# ProPrj_RetroGame_2024-09-02_00-02-09_202.net
KiCad netlist of a schematic drawn in EasyEDA Pro
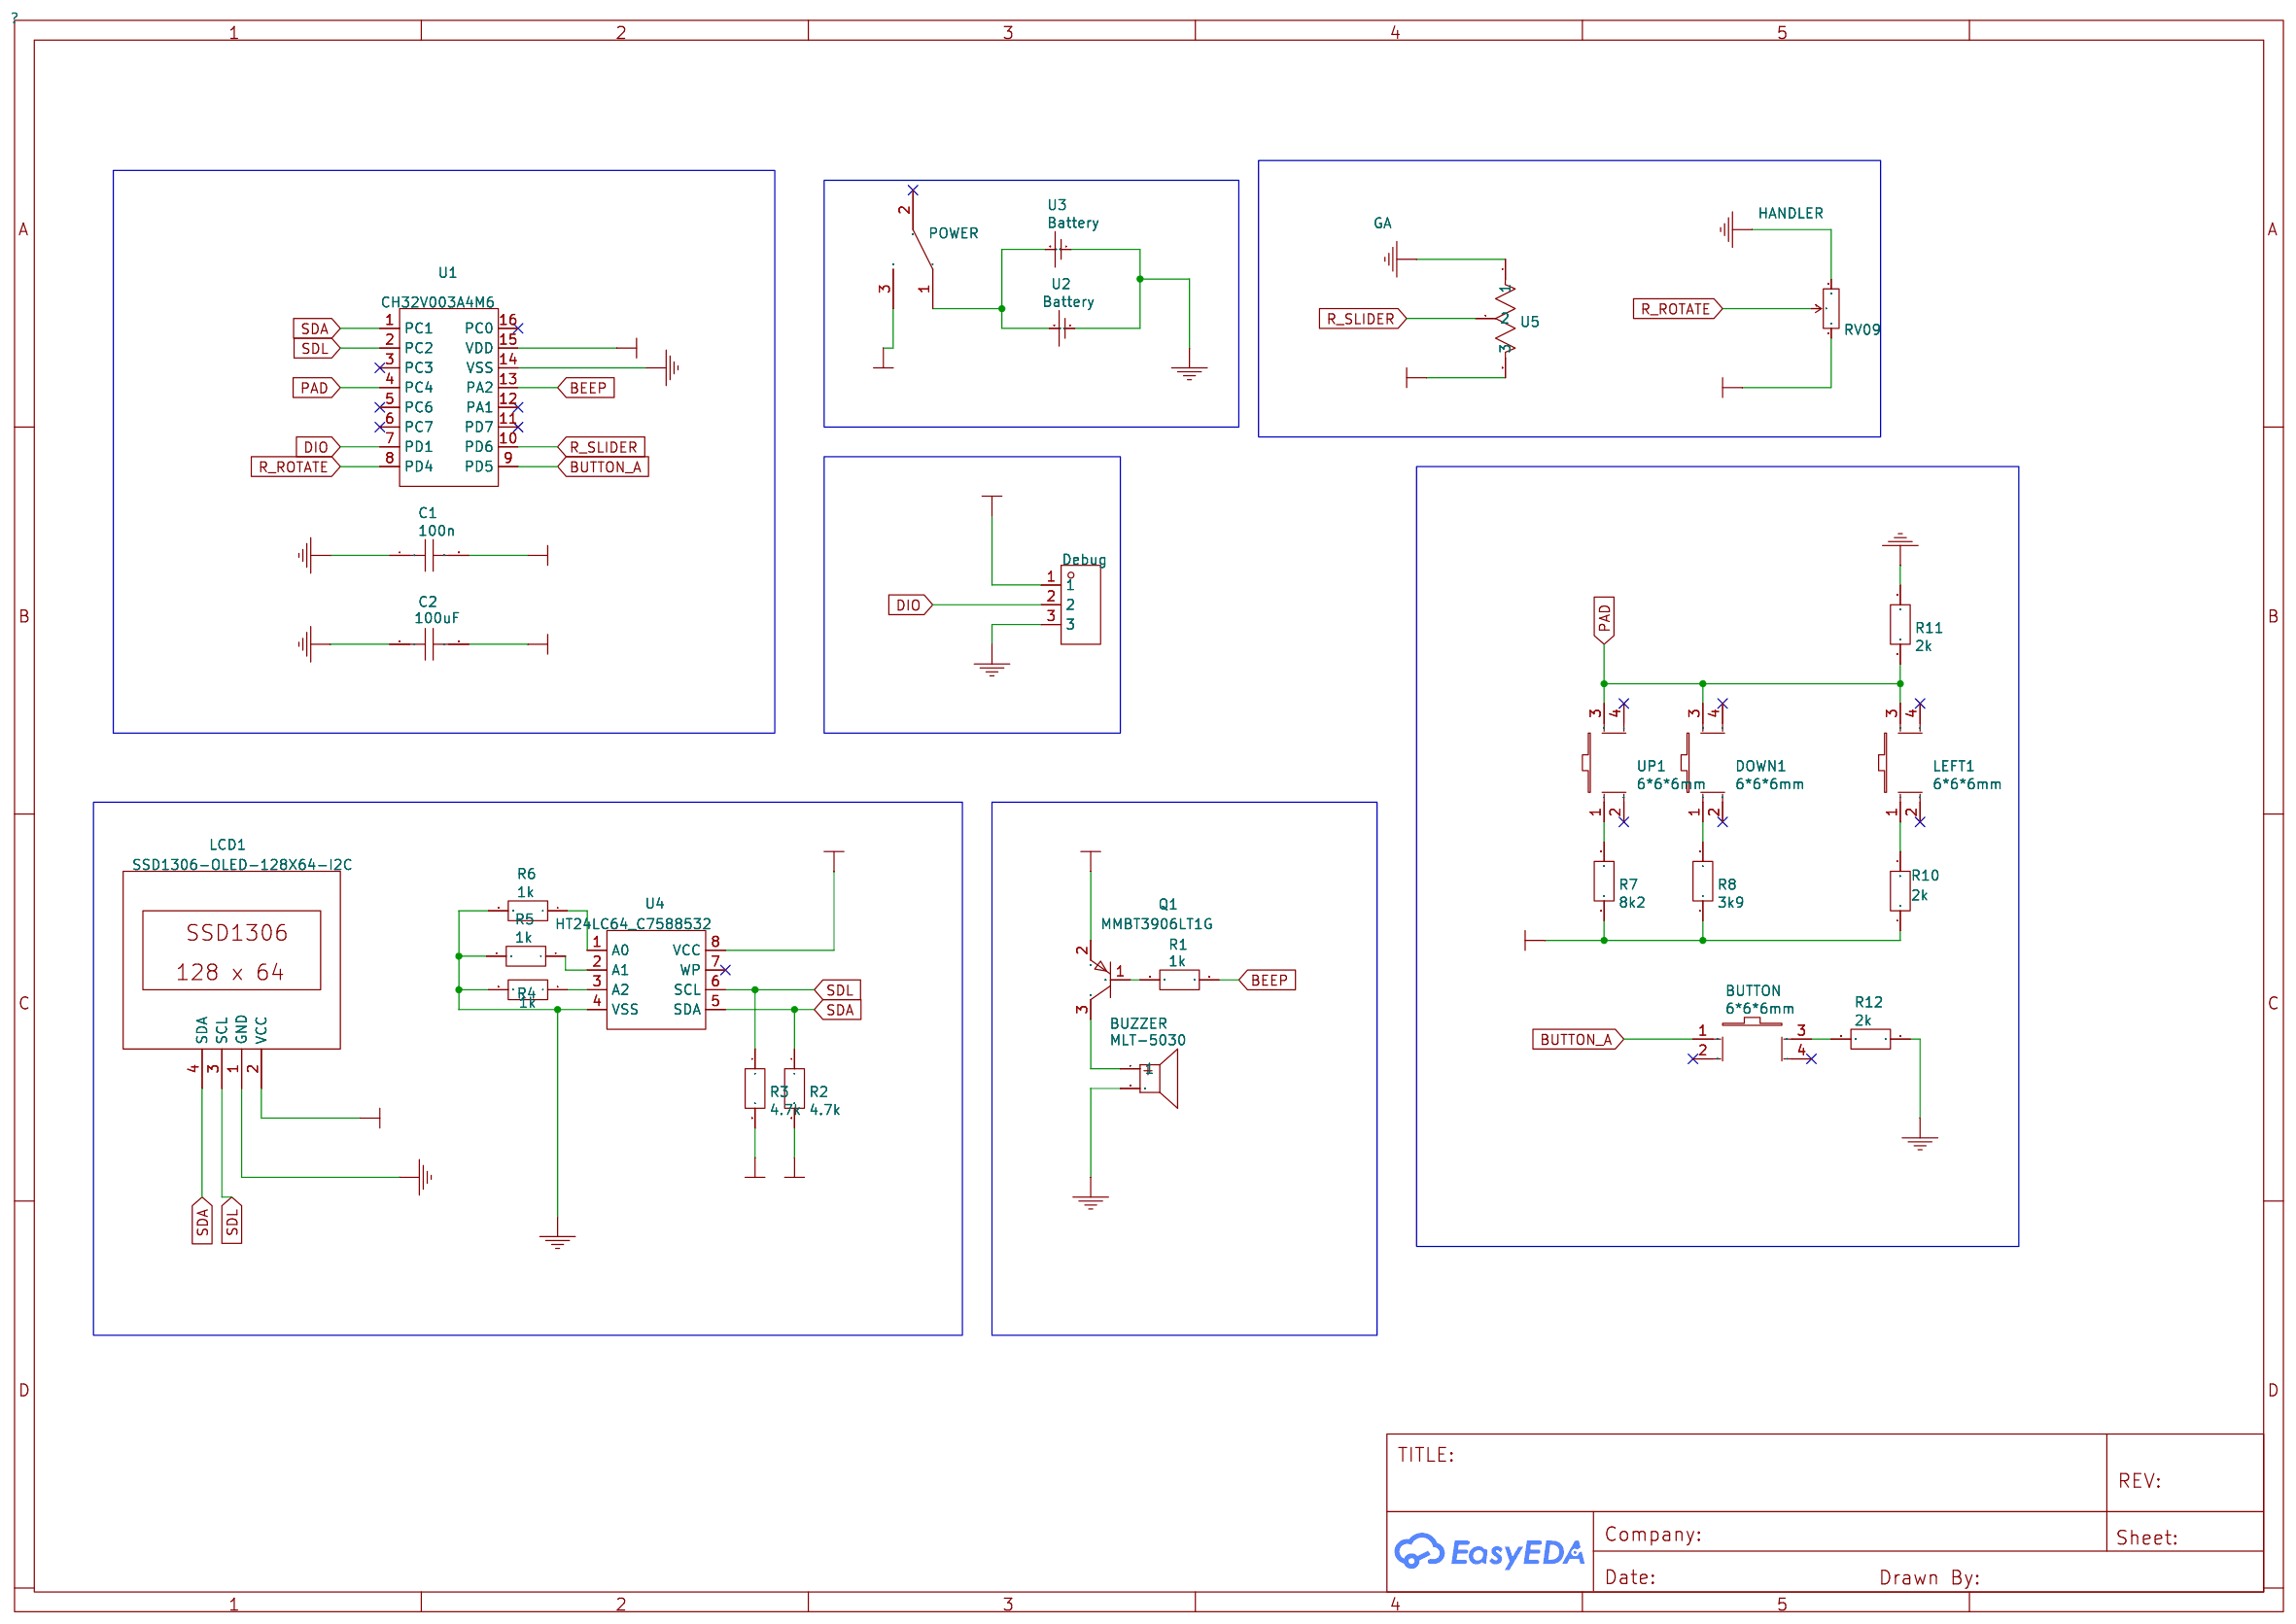
[diagram p0: schematic sheet]

(export (version "E")
  (design (tool "Eeschema 10.0.6"))
  (components
    (comp (ref "BUTTON")
      (value "6*6*6mm")
      (footprint "easyedapro:KEY-6.0*6.0")
      (fields
        (field (name "Manufacturer Part") "SMD Tactile Switch6*6*6mm")
        (field (name "Manufacturer") "ReliaPro")
      )
      (libsource (lib "easyedapro") (part "6*6*6mm"))
    )
    (comp (ref "BUZZER")
      (value "MLT-5030")
      (footprint "easyedapro:B-5.2*5.2")
      (fields (field (name "Manufacturer") "HNDZ"))
      (libsource (lib "easyedapro") (part "MLT-5030"))
    )
    (comp (ref "C1")
      (value "100n")
      (footprint "easyedapro:C0603")
      (libsource (lib "easyedapro") (part "100n"))
    )
    (comp (ref "C2")
      (value "100uF")
      (footprint "easyedapro:C0603")
      (libsource (lib "easyedapro") (part "100uF"))
    )
    (comp (ref "Debug")
      (value "~")
      (footprint "easyedapro:HDR-TH_3P-P2.54-V-F")
      (libsource (lib "easyedapro") (part "PM254V-11-03-H85"))
    )
    (comp (ref "DOWN1")
      (value "6*6*6mm")
      (footprint "easyedapro:KEY-6.0*6.0")
      (fields
        (field (name "Manufacturer Part") "SMD Tactile Switch6*6*6mm")
        (field (name "Manufacturer") "ReliaPro")
      )
      (libsource (lib "easyedapro") (part "6*6*6mm"))
    )
    (comp (ref "HANDLER")
      (value "RV09")
      (footprint "easyedapro:RV09")
      (libsource (lib "easyedapro") (part "RV09"))
    )
    (comp (ref "LCD1")
      (value "SSD1306-OLED-128X64-I2C")
      (footprint "easyedapro:SSD1306-OLED-128X64-I2C")
      (libsource (lib "easyedapro") (part "SSD1306-OLED-128X64-I2C"))
    )
    (comp (ref "LEFT1")
      (value "6*6*6mm")
      (footprint "easyedapro:KEY-6.0*6.0")
      (fields
        (field (name "Manufacturer Part") "SMD Tactile Switch6*6*6mm")
        (field (name "Manufacturer") "ReliaPro")
      )
      (libsource (lib "easyedapro") (part "6*6*6mm"))
    )
    (comp (ref "POWER")
      (value "MINI SLIDE SWITCH")
      (footprint "easyedapro:MINI SLIDE SWITCH SPDT - 3PİN - 2.54MM - 11X5.5MM - SS12D00G3-FP")
      (fields
        (field (name "Manufacturer Part") "COM-00102")
        (field (name "Manufacturer") "SparkFun Electronics")
      )
      (libsource (lib "easyedapro") (part "MINI SLIDE SWITCH"))
    )
    (comp (ref "Q1")
      (value "MMBT3906LT1G")
      (footprint "easyedapro:PADS_SOT23-132")
      (libsource (lib "easyedapro") (part "MMBT3906LT1G"))
    )
    (comp (ref "R1") (value "1k") (footprint "easyedapro:R0603") (libsource (lib "easyedapro") (part "1k")))
    (comp (ref "R2")
      (value "4.7k")
      (footprint "easyedapro:R0603")
      (libsource (lib "easyedapro") (part "4.7k"))
    )
    (comp (ref "R3")
      (value "4.7k")
      (footprint "easyedapro:R0603")
      (libsource (lib "easyedapro") (part "4.7k"))
    )
    (comp (ref "R4") (value "1k") (footprint "easyedapro:R0603") (libsource (lib "easyedapro") (part "1k")))
    (comp (ref "R5") (value "1k") (footprint "easyedapro:R0603") (libsource (lib "easyedapro") (part "1k")))
    (comp (ref "R6") (value "1k") (footprint "easyedapro:R0603") (libsource (lib "easyedapro") (part "1k")))
    (comp (ref "R7")
      (value "8k2")
      (footprint "easyedapro:0603")
      (fields (field (name "Manufacturer Part") "0603WAF8201T5E") (field (name "Manufacturer") "UniOhm"))
      (libsource (lib "easyedapro") (part "8k2"))
    )
    (comp (ref "R8")
      (value "3k9")
      (footprint "easyedapro:0603")
      (fields (field (name "Manufacturer Part") "0603WAF3901T5E") (field (name "Manufacturer") "UniOhm"))
      (libsource (lib "easyedapro") (part "3k9"))
    )
    (comp (ref "R10")
      (value "2k")
      (footprint "easyedapro:0603")
      (fields (field (name "Manufacturer Part") "0603WAF2001T5E") (field (name "Manufacturer") "UniOhm"))
      (libsource (lib "easyedapro") (part "2k"))
    )
    (comp (ref "R11")
      (value "2k")
      (footprint "easyedapro:0603")
      (fields (field (name "Manufacturer Part") "0603WAF2001T5E") (field (name "Manufacturer") "UniOhm"))
      (libsource (lib "easyedapro") (part "2k"))
    )
    (comp (ref "R12")
      (value "2k")
      (footprint "easyedapro:0603")
      (fields (field (name "Manufacturer Part") "0603WAF2001T5E") (field (name "Manufacturer") "UniOhm"))
      (libsource (lib "easyedapro") (part "2k"))
    )
    (comp (ref "U1")
      (value "CH32V003A4M6")
      (footprint "easyedapro:SOIC-16_L9.9-W3.9-P1.27-LS6.0-BL")
      (fields (field (name "Manufacturer") "WCH(南京沁恒)"))
      (libsource (lib "easyedapro") (part "CH32V003A4M6"))
    )
    (comp (ref "U2")
      (value "Battery")
      (footprint "easyedapro:BATTERY-SMD-MY-2032")
      (fields (field (name "Manufacturer Part") "MY-2032-10") (field (name "Manufacturer") "MYOUNG(美阳)"))
      (libsource (lib "easyedapro") (part "Battery"))
    )
    (comp (ref "U3")
      (value "Battery")
      (footprint "easyedapro:BATTERY-SMD-MY-2032")
      (fields (field (name "Manufacturer Part") "MY-2032-10") (field (name "Manufacturer") "MYOUNG(美阳)"))
      (libsource (lib "easyedapro") (part "Battery"))
    )
    (comp (ref "U4")
      (value "HT24LC64_C7588532")
      (footprint "easyedapro:SOP-8_L4.9-W3.9-P1.27-LS6.0-BL")
      (fields (field (name "Manufacturer Part") "HT24LC64") (field (name "Manufacturer") "HOLTEK(合泰/盛群)"))
      (libsource (lib "easyedapro") (part "HT24LC64_C7588532"))
    )
    (comp (ref "U5")
      (value "GA")
      (footprint "easyedapro:PSM050S-10B10KB")
      (fields
        (field (name "Manufacturer Part") "PSM050S-10B10KB")
        (field (name "Manufacturer") "TT Electronics")
      )
      (libsource (lib "easyedapro") (part "GA"))
    )
    (comp (ref "UP1")
      (value "6*6*6mm")
      (footprint "easyedapro:KEY-6.0*6.0")
      (fields
        (field (name "Manufacturer Part") "SMD Tactile Switch6*6*6mm")
        (field (name "Manufacturer") "ReliaPro")
      )
      (libsource (lib "easyedapro") (part "6*6*6mm"))
    )
  )
  (nets
    (net (code "1") (name "BEEP") (class "Default")
      (node (ref "R1") (pin "1") (pinfunction "1_1") (pintype "unspecified"))
      (node (ref "U1") (pin "13") (pinfunction "PA2_13") (pintype "unspecified"))
    )
    (net (code "2") (name "BUTTON_A") (class "Default")
      (node (ref "BUTTON") (pin "1") (pinfunction "1_1") (pintype "input"))
      (node (ref "U1") (pin "9") (pinfunction "PD5_9") (pintype "unspecified"))
    )
    (net (code "3") (name "DIO") (class "Default")
      (node (ref "Debug") (pin "2") (pinfunction "2_2") (pintype "unspecified"))
      (node (ref "U1") (pin "7") (pinfunction "PD1_7") (pintype "unspecified"))
    )
    (net (code "4") (name "GND") (class "Default")
      (node (ref "BUZZER") (pin "2") (pinfunction "2_2") (pintype "unspecified"))
      (node (ref "C1") (pin "1") (pinfunction "1_1") (pintype "unspecified"))
      (node (ref "C2") (pin "1") (pinfunction "1_1") (pintype "unspecified"))
      (node (ref "Debug") (pin "3") (pinfunction "3_3") (pintype "unspecified"))
      (node (ref "HANDLER") (pin "3") (pinfunction "3_3") (pintype "unspecified"))
      (node (ref "LCD1") (pin "1") (pinfunction "GND_1") (pintype "unspecified"))
      (node (ref "R11") (pin "2") (pinfunction "2_2") (pintype "unspecified"))
      (node (ref "R12") (pin "1") (pinfunction "1_1") (pintype "unspecified"))
      (node (ref "R4") (pin "2") (pinfunction "2_2") (pintype "unspecified"))
      (node (ref "R5") (pin "2") (pinfunction "2_2") (pintype "unspecified"))
      (node (ref "R6") (pin "2") (pinfunction "2_2") (pintype "unspecified"))
      (node (ref "U1") (pin "14") (pinfunction "VSS_14") (pintype "unspecified"))
      (node (ref "U2") (pin "1") (pinfunction "1_1") (pintype "input"))
      (node (ref "U3") (pin "1") (pinfunction "1_1") (pintype "input"))
      (node (ref "U4") (pin "4") (pinfunction "VSS_4") (pintype "unspecified"))
      (node (ref "U5") (pin "1") (pinfunction "1_1") (pintype "unspecified"))
    )
    (net (code "5") (name "Net-(BUTTON-Pad3)") (class "Default")
      (node (ref "BUTTON") (pin "3") (pinfunction "3_3") (pintype "input"))
      (node (ref "R12") (pin "2") (pinfunction "2_2") (pintype "unspecified"))
    )
    (net (code "6") (name "Net-(DOWN1-Pad1)") (class "Default")
      (node (ref "DOWN1") (pin "1") (pinfunction "1_1") (pintype "input"))
      (node (ref "R8") (pin "2") (pinfunction "2_2") (pintype "unspecified"))
    )
    (net (code "7") (name "Net-(LEFT1-Pad1)") (class "Default")
      (node (ref "LEFT1") (pin "1") (pinfunction "1_1") (pintype "input"))
      (node (ref "R10") (pin "2") (pinfunction "2_2") (pintype "unspecified"))
    )
    (net (code "8") (name "Net-(POWER-Pad1)") (class "Default")
      (node (ref "POWER") (pin "1") (pinfunction "1_1") (pintype "unspecified"))
      (node (ref "U2") (pin "2") (pinfunction "2_2") (pintype "input"))
      (node (ref "U3") (pin "2") (pinfunction "2_2") (pintype "input"))
    )
    (net (code "9") (name "Net-(Q1-B)") (class "Default")
      (node (ref "Q1") (pin "1") (pinfunction "B_1") (pintype "unspecified"))
      (node (ref "R1") (pin "2") (pinfunction "2_2") (pintype "unspecified"))
    )
    (net (code "10") (name "Net-(Q1-C)") (class "Default")
      (node (ref "BUZZER") (pin "1") (pinfunction "1_1") (pintype "unspecified"))
      (node (ref "Q1") (pin "3") (pinfunction "C_3") (pintype "unspecified"))
    )
    (net (code "11") (name "Net-(R7-Pad2)") (class "Default")
      (node (ref "R7") (pin "2") (pinfunction "2_2") (pintype "unspecified"))
      (node (ref "UP1") (pin "1") (pinfunction "1_1") (pintype "input"))
    )
    (net (code "12") (name "Net-(U4-A0)") (class "Default")
      (node (ref "R6") (pin "1") (pinfunction "1_1") (pintype "unspecified"))
      (node (ref "U4") (pin "1") (pinfunction "A0_1") (pintype "unspecified"))
    )
    (net (code "13") (name "Net-(U4-A1)") (class "Default")
      (node (ref "R5") (pin "1") (pinfunction "1_1") (pintype "unspecified"))
      (node (ref "U4") (pin "2") (pinfunction "A1_2") (pintype "unspecified"))
    )
    (net (code "14") (name "Net-(U4-A2)") (class "Default")
      (node (ref "R4") (pin "1") (pinfunction "1_1") (pintype "unspecified"))
      (node (ref "U4") (pin "3") (pinfunction "A2_3") (pintype "unspecified"))
    )
    (net (code "15") (name "PAD") (class "Default")
      (node (ref "DOWN1") (pin "3") (pinfunction "3_3") (pintype "input"))
      (node (ref "LEFT1") (pin "3") (pinfunction "3_3") (pintype "input"))
      (node (ref "R11") (pin "1") (pinfunction "1_1") (pintype "unspecified"))
      (node (ref "U1") (pin "4") (pinfunction "PC4_4") (pintype "unspecified"))
      (node (ref "UP1") (pin "3") (pinfunction "3_3") (pintype "input"))
    )
    (net (code "16") (name "R_ROTATE") (class "Default")
      (node (ref "HANDLER") (pin "2") (pinfunction "2_2") (pintype "unspecified"))
      (node (ref "U1") (pin "8") (pinfunction "PD4_8") (pintype "unspecified"))
    )
    (net (code "17") (name "R_SLIDER") (class "Default")
      (node (ref "U1") (pin "10") (pinfunction "PD6_10") (pintype "unspecified"))
      (node (ref "U5") (pin "2") (pinfunction "2_2") (pintype "unspecified"))
    )
    (net (code "18") (name "SDA") (class "Default")
      (node (ref "LCD1") (pin "4") (pinfunction "SDA_4") (pintype "unspecified"))
      (node (ref "R2") (pin "1") (pinfunction "1_1") (pintype "unspecified"))
      (node (ref "U1") (pin "1") (pinfunction "PC1_1") (pintype "unspecified"))
      (node (ref "U4") (pin "5") (pinfunction "SDA_5") (pintype "unspecified"))
    )
    (net (code "19") (name "SDL") (class "Default")
      (node (ref "LCD1") (pin "3") (pinfunction "SCL_3") (pintype "unspecified"))
      (node (ref "R3") (pin "1") (pinfunction "1_1") (pintype "unspecified"))
      (node (ref "U1") (pin "2") (pinfunction "PC2_2") (pintype "unspecified"))
      (node (ref "U4") (pin "6") (pinfunction "SCL_6") (pintype "unspecified"))
    )
    (net (code "20") (name "VCC") (class "Default")
      (node (ref "C1") (pin "2") (pinfunction "2_2") (pintype "unspecified"))
      (node (ref "C2") (pin "2") (pinfunction "2_2") (pintype "unspecified"))
      (node (ref "Debug") (pin "1") (pinfunction "1_1") (pintype "unspecified"))
      (node (ref "HANDLER") (pin "1") (pinfunction "1_1") (pintype "unspecified"))
      (node (ref "LCD1") (pin "2") (pinfunction "VCC_2") (pintype "unspecified"))
      (node (ref "POWER") (pin "3") (pinfunction "3_3") (pintype "unspecified"))
      (node (ref "Q1") (pin "2") (pinfunction "E_2") (pintype "unspecified"))
      (node (ref "R10") (pin "1") (pinfunction "1_1") (pintype "unspecified"))
      (node (ref "R2") (pin "2") (pinfunction "2_2") (pintype "unspecified"))
      (node (ref "R3") (pin "2") (pinfunction "2_2") (pintype "unspecified"))
      (node (ref "R7") (pin "1") (pinfunction "1_1") (pintype "unspecified"))
      (node (ref "R8") (pin "1") (pinfunction "1_1") (pintype "unspecified"))
      (node (ref "U1") (pin "15") (pinfunction "VDD_15") (pintype "unspecified"))
      (node (ref "U4") (pin "8") (pinfunction "VCC_8") (pintype "unspecified"))
      (node (ref "U5") (pin "3") (pinfunction "3_3") (pintype "unspecified"))
    )
    (net (code "21") (name "unconnected-(BUTTON-Pad2)") (class "Default")
      (node (ref "BUTTON") (pin "2") (pinfunction "2_2") (pintype "input+no_connect"))
    )
    (net (code "22") (name "unconnected-(BUTTON-Pad4)") (class "Default")
      (node (ref "BUTTON") (pin "4") (pinfunction "4_4") (pintype "input+no_connect"))
    )
    (net (code "23") (name "unconnected-(DOWN1-Pad2)") (class "Default")
      (node (ref "DOWN1") (pin "2") (pinfunction "2_2") (pintype "input+no_connect"))
    )
    (net (code "24") (name "unconnected-(DOWN1-Pad4)") (class "Default")
      (node (ref "DOWN1") (pin "4") (pinfunction "4_4") (pintype "input+no_connect"))
    )
    (net (code "25") (name "unconnected-(LEFT1-Pad2)") (class "Default")
      (node (ref "LEFT1") (pin "2") (pinfunction "2_2") (pintype "input+no_connect"))
    )
    (net (code "26") (name "unconnected-(LEFT1-Pad4)") (class "Default")
      (node (ref "LEFT1") (pin "4") (pinfunction "4_4") (pintype "input+no_connect"))
    )
    (net (code "27") (name "unconnected-(POWER-Pad2)") (class "Default")
      (node (ref "POWER") (pin "2") (pinfunction "2_2") (pintype "unspecified+no_connect"))
    )
    (net (code "28") (name "unconnected-(U1-PA1-Pad12)") (class "Default")
      (node (ref "U1") (pin "12") (pinfunction "PA1_12") (pintype "unspecified+no_connect"))
    )
    (net (code "29") (name "unconnected-(U1-PC0-Pad16)") (class "Default")
      (node (ref "U1") (pin "16") (pinfunction "PC0_16") (pintype "unspecified+no_connect"))
    )
    (net (code "30") (name "unconnected-(U1-PC3-Pad3)") (class "Default")
      (node (ref "U1") (pin "3") (pinfunction "PC3_3") (pintype "unspecified+no_connect"))
    )
    (net (code "31") (name "unconnected-(U1-PC6-Pad5)") (class "Default")
      (node (ref "U1") (pin "5") (pinfunction "PC6_5") (pintype "unspecified+no_connect"))
    )
    (net (code "32") (name "unconnected-(U1-PC7-Pad6)") (class "Default")
      (node (ref "U1") (pin "6") (pinfunction "PC7_6") (pintype "unspecified+no_connect"))
    )
    (net (code "33") (name "unconnected-(U1-PD7-Pad11)") (class "Default")
      (node (ref "U1") (pin "11") (pinfunction "PD7_11") (pintype "unspecified+no_connect"))
    )
    (net (code "34") (name "unconnected-(U4-WP-Pad7)") (class "Default")
      (node (ref "U4") (pin "7") (pinfunction "WP_7") (pintype "unspecified+no_connect"))
    )
    (net (code "35") (name "unconnected-(UP1-Pad2)") (class "Default")
      (node (ref "UP1") (pin "2") (pinfunction "2_2") (pintype "input+no_connect"))
    )
    (net (code "36") (name "unconnected-(UP1-Pad4)") (class "Default")
      (node (ref "UP1") (pin "4") (pinfunction "4_4") (pintype "input+no_connect"))
    )
  )
)
